# STM32G473CET6_PINOUT.net
KiCad netlist of a schematic drawn in Altium Designer
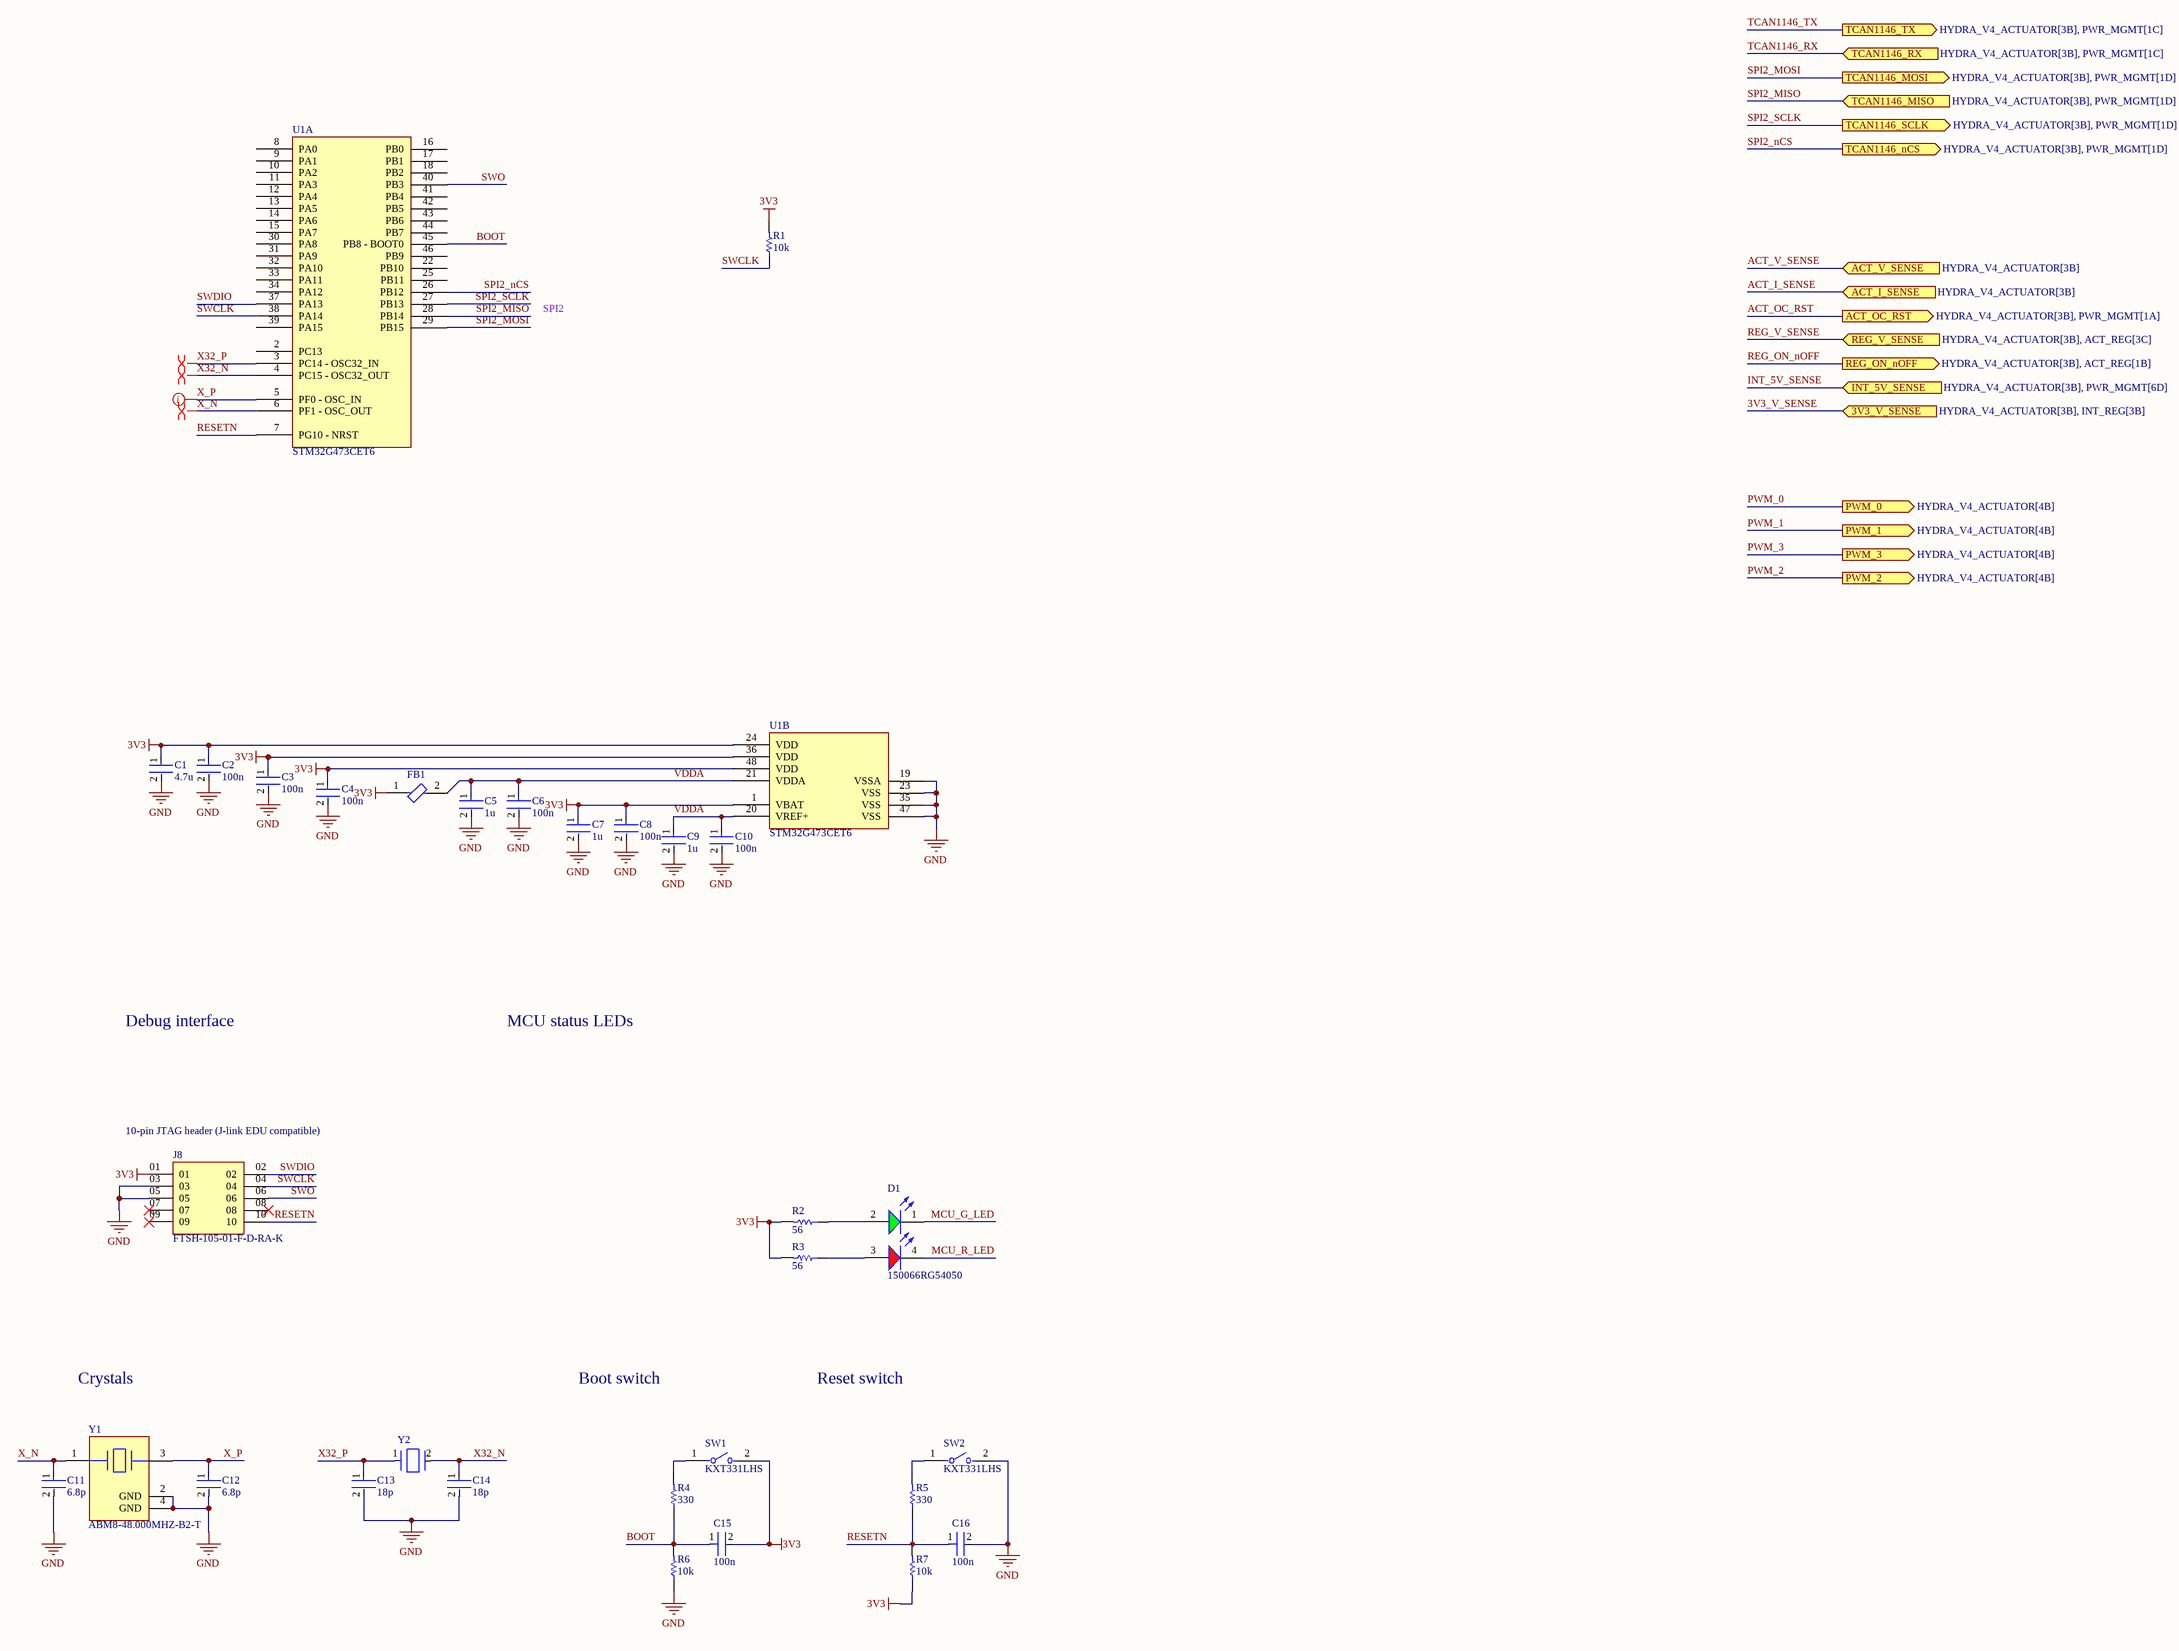
[diagram p0: STM32G473CET6_PINOUT.SchDoc]

(export (version "E")
  (design (tool "Eeschema 10.0.6"))
  (components
    (comp (ref "C1")
      (value "4.7u")
      (footprint "FP-0402-L_1_0_0_05-W_0_5-IPC_A")
      (description "LARGE PADS, 0402 CAP, CHANGE COMMENT TO MATCH REAL P/N")
      (libsource (lib "Space Concordia") (part "b4654b650e69147ec39a6b967a45e02"))
    )
    (comp (ref "C2")
      (value "100n")
      (footprint "FP-0402-L_1_0_0_05-W_0_5-IPC_A")
      (description "LARGE PADS, 0402 CAP, CHANGE COMMENT TO MATCH REAL P/N")
      (libsource (lib "Space Concordia") (part "b4654b650e69147ec39a6b967a45e02"))
    )
    (comp (ref "C3")
      (value "100n")
      (footprint "FP-0402-L_1_0_0_05-W_0_5-IPC_A")
      (description "LARGE PADS, 0402 CAP, CHANGE COMMENT TO MATCH REAL P/N")
      (libsource (lib "Space Concordia") (part "b4654b650e69147ec39a6b967a45e02"))
    )
    (comp (ref "C4")
      (value "100n")
      (footprint "FP-0402-L_1_0_0_05-W_0_5-IPC_A")
      (description "LARGE PADS, 0402 CAP, CHANGE COMMENT TO MATCH REAL P/N")
      (libsource (lib "Space Concordia") (part "b4654b650e69147ec39a6b967a45e02"))
    )
    (comp (ref "C5")
      (value "1u")
      (footprint "FP-0402-L_1_0_0_05-W_0_5-IPC_A")
      (description "LARGE PADS, 0402 CAP, CHANGE COMMENT TO MATCH REAL P/N")
      (libsource (lib "Space Concordia") (part "b4654b650e69147ec39a6b967a45e02"))
    )
    (comp (ref "C6")
      (value "100n")
      (footprint "FP-0402-L_1_0_0_05-W_0_5-IPC_A")
      (description "LARGE PADS, 0402 CAP, CHANGE COMMENT TO MATCH REAL P/N")
      (libsource (lib "Space Concordia") (part "b4654b650e69147ec39a6b967a45e02"))
    )
    (comp (ref "C7")
      (value "1u")
      (footprint "FP-0402-L_1_0_0_05-W_0_5-IPC_A")
      (description "LARGE PADS, 0402 CAP, CHANGE COMMENT TO MATCH REAL P/N")
      (libsource (lib "Space Concordia") (part "b4654b650e69147ec39a6b967a45e02"))
    )
    (comp (ref "C8")
      (value "100n")
      (footprint "FP-0402-L_1_0_0_05-W_0_5-IPC_A")
      (description "LARGE PADS, 0402 CAP, CHANGE COMMENT TO MATCH REAL P/N")
      (libsource (lib "Space Concordia") (part "b4654b650e69147ec39a6b967a45e02"))
    )
    (comp (ref "C9")
      (value "1u")
      (footprint "FP-0402-L_1_0_0_05-W_0_5-IPC_A")
      (description "LARGE PADS, 0402 CAP, CHANGE COMMENT TO MATCH REAL P/N")
      (libsource (lib "Space Concordia") (part "b4654b650e69147ec39a6b967a45e02"))
    )
    (comp (ref "C10")
      (value "100n")
      (footprint "FP-0402-L_1_0_0_05-W_0_5-IPC_A")
      (description "LARGE PADS, 0402 CAP, CHANGE COMMENT TO MATCH REAL P/N")
      (libsource (lib "Space Concordia") (part "b4654b650e69147ec39a6b967a45e02"))
    )
    (comp (ref "C11")
      (value "6.8p")
      (footprint "FP-0402-L_1_0_0_05-W_0_5-IPC_A")
      (description "LARGE PADS, 0402 CAP, CHANGE COMMENT TO MATCH REAL P/N")
      (libsource (lib "Space Concordia") (part "b4654b650e69147ec39a6b967a45e02"))
    )
    (comp (ref "C12")
      (value "6.8p")
      (footprint "FP-0402-L_1_0_0_05-W_0_5-IPC_A")
      (description "LARGE PADS, 0402 CAP, CHANGE COMMENT TO MATCH REAL P/N")
      (libsource (lib "Space Concordia") (part "b4654b650e69147ec39a6b967a45e02"))
    )
    (comp (ref "C13")
      (value "18p")
      (footprint "FP-0402-L_1_0_0_05-W_0_5-IPC_A")
      (description "LARGE PADS, 0402 CAP, CHANGE COMMENT TO MATCH REAL P/N")
      (libsource (lib "Space Concordia") (part "b4654b650e69147ec39a6b967a45e02"))
    )
    (comp (ref "C14")
      (value "18p")
      (footprint "FP-0402-L_1_0_0_05-W_0_5-IPC_A")
      (description "LARGE PADS, 0402 CAP, CHANGE COMMENT TO MATCH REAL P/N")
      (libsource (lib "Space Concordia") (part "b4654b650e69147ec39a6b967a45e02"))
    )
    (comp (ref "C15")
      (value "100n")
      (footprint "FP-0402-L_1_0_0_05-W_0_5-IPC_A")
      (description "LARGE PADS, 0402 CAP, CHANGE COMMENT TO MATCH REAL P/N")
      (libsource (lib "Space Concordia") (part "b4654b650e69147ec39a6b967a45e02"))
    )
    (comp (ref "C16")
      (value "100n")
      (footprint "FP-0402-L_1_0_0_05-W_0_5-IPC_A")
      (description "LARGE PADS, 0402 CAP, CHANGE COMMENT TO MATCH REAL P/N")
      (libsource (lib "Space Concordia") (part "b4654b650e69147ec39a6b967a45e02"))
    )
    (comp (ref "D1")
      (value "150066RG54050")
      (footprint "WL-SBCD_0606")
      (description "Led, Red/Grn, 180Mcd/230Mcd, 624Nm/525Nm Rohs Compliant: Yes")
      (fields (field (name "SOURCE") "rgled.SchLib"))
      (libsource (lib "Space Concordia") (part "CMP-004-00034-2"))
    )
    (comp (ref "FB1")
      (value "BLM15PX601SN1D")
      (footprint "FP-BLM15-0_05-MFG")
      (description "Chip Ferrite Bead, 0402, 600Ω @ 100MHz, 0.23Ω, 25%, 900mA")
      (fields (field (name "TOLERANCE") "25%"))
      (libsource (lib "Altium Content Vault") (part "5f30dd21d616792df468990f7003faa"))
    )
    (comp (ref "J8")
      (value "FTSH-105-01-F-D-RA-K")
      (footprint "FTSH-105-01-F-D-RA-K-Footprint-1")
      (libsource (lib "Space Concordia") (part "FTSH-105-01-F-D-RA-K-Symbol-1"))
    )
    (comp (ref "R1")
      (value "10k")
      (footprint "R0603B")
      (description "Resistor")
      (libsource (lib "Space Concordia") (part "Resistor"))
    )
    (comp (ref "R2")
      (value "56")
      (footprint "R0603B")
      (description "Resistor")
      (libsource (lib "Space Concordia") (part "Resistor"))
    )
    (comp (ref "R3")
      (value "56")
      (footprint "R0603B")
      (description "Resistor")
      (libsource (lib "Space Concordia") (part "Resistor"))
    )
    (comp (ref "R4")
      (value "330")
      (footprint "R0603B")
      (description "Resistor")
      (libsource (lib "Space Concordia") (part "Resistor"))
    )
    (comp (ref "R5")
      (value "330")
      (footprint "R0603B")
      (description "Resistor")
      (libsource (lib "Space Concordia") (part "Resistor"))
    )
    (comp (ref "R6")
      (value "10k")
      (footprint "R0603B")
      (description "Resistor")
      (libsource (lib "Space Concordia") (part "Resistor"))
    )
    (comp (ref "R7")
      (value "10k")
      (footprint "R0603B")
      (description "Resistor")
      (libsource (lib "Space Concordia") (part "Resistor"))
    )
    (comp (ref "SW1")
      (value "KXT331LHS")
      (footprint "FP-KXT331LHS-MFG")
      (description "SWITCH TACTILE SPST-NO 0.02A 15V")
      (libsource (lib "Altium Content Vault") (part "bb27bde45df87f1f469753f287ef5ae"))
    )
    (comp (ref "SW2")
      (value "KXT331LHS")
      (footprint "FP-KXT331LHS-MFG")
      (description "SWITCH TACTILE SPST-NO 0.02A 15V")
      (libsource (lib "Altium Content Vault") (part "bb27bde45df87f1f469753f287ef5ae"))
    )
    (comp (ref "U1")
      (value "STM32G473CET6")
      (footprint "TSQFP50P900X900X160-48N")
      (description "RISC Microcontroller, 32-Bit, 170MHz")
      (libsource (lib "Space Concordia") (part "STM32G473CET6"))
    )
    (comp (ref "Y1")
      (value "ABM8-48.000MHZ-B2-T")
      (footprint "FP-ABM8-MFG")
      (description "Crystal 48MHz ±20ppm 18pF SMD-4 3.2mm x 2.5mm")
      (fields (field (name "TOLERANCE") "20ppm"))
      (libsource (lib "Altium Content Vault") (part "dfdb7f9a12507849fb681da9a70121c"))
    )
    (comp (ref "Y2")
      (value "ECS-.327-12.5-1210-TR")
      (footprint "FP-ECX-1210-MFG")
      (description "CRYSTAL 32.7680KHZ 12.5PF SMD")
      (fields
        (field (name "OCTOPART") "https://octopart.com/ecs-.327-12.5-1210-tr-ecs+international-81221340")
        (field (name "TOLERANCE") "20ppm")
      )
      (libsource (lib "Altium Content Vault") (part "99724985039315a44fd0d1401b84e49"))
    )
  )
  (nets
    (net (code "5") (name "/BOOT") (class "Default")
      (node (ref "C15") (pin "1") (pinfunction "1_1") (pintype "passive"))
      (node (ref "R4") (pin "1") (pinfunction "1_1") (pintype "passive"))
      (node (ref "R6") (pin "2") (pinfunction "2_2") (pintype "passive"))
      (node (ref "U1") (pin "45") (pinfunction "PB8_-_BOOT0_45") (pintype "passive"))
    )
    (net (code "7") (name "/MCU_G_LED") (class "Default")
      (node (ref "D1") (pin "1") (pinfunction "K_1") (pintype "passive"))
    )
    (net (code "8") (name "/MCU_R_LED") (class "Default")
      (node (ref "D1") (pin "4") (pinfunction "K_4") (pintype "passive"))
    )
    (net (code "15") (name "/RESETN") (class "Default")
      (node (ref "C16") (pin "1") (pinfunction "1_1") (pintype "passive"))
      (node (ref "J8") (pin "10") (pinfunction "10_10") (pintype "passive"))
      (node (ref "R5") (pin "1") (pinfunction "1_1") (pintype "passive"))
      (node (ref "R7") (pin "2") (pinfunction "2_2") (pintype "passive"))
      (node (ref "U1") (pin "7") (pinfunction "PG10_-_NRST_7") (pintype "passive"))
    )
    (net (code "16") (name "/SPI2_MISO") (class "Default")
      (node (ref "U1") (pin "28") (pinfunction "PB14_28") (pintype "passive"))
    )
    (net (code "17") (name "/SPI2_MOSI") (class "Default")
      (node (ref "U1") (pin "29") (pinfunction "PB15_29") (pintype "passive"))
    )
    (net (code "18") (name "/SPI2_SCLK") (class "Default")
      (node (ref "U1") (pin "27") (pinfunction "PB13_27") (pintype "passive"))
    )
    (net (code "19") (name "/SPI2_nCS") (class "Default")
      (node (ref "U1") (pin "26") (pinfunction "PB12_26") (pintype "passive"))
    )
    (net (code "20") (name "/SWCLK") (class "Default")
      (node (ref "J8") (pin "04") (pinfunction "04_04") (pintype "passive"))
      (node (ref "R1") (pin "1") (pinfunction "1_1") (pintype "passive"))
      (node (ref "U1") (pin "38") (pinfunction "PA14_38") (pintype "passive"))
    )
    (net (code "21") (name "/SWDIO") (class "Default")
      (node (ref "J8") (pin "02") (pinfunction "02_02") (pintype "passive"))
      (node (ref "U1") (pin "37") (pinfunction "PA13_37") (pintype "passive"))
    )
    (net (code "22") (name "/SWO") (class "Default")
      (node (ref "J8") (pin "06") (pinfunction "06_06") (pintype "passive"))
      (node (ref "U1") (pin "40") (pinfunction "PB3_40") (pintype "passive"))
    )
    (net (code "25") (name "/VDDA") (class "Default")
      (node (ref "C10") (pin "1") (pinfunction "1_1") (pintype "passive"))
      (node (ref "C5") (pin "1") (pinfunction "1_1") (pintype "passive"))
      (node (ref "C6") (pin "1") (pinfunction "1_1") (pintype "passive"))
      (node (ref "C9") (pin "1") (pinfunction "1_1") (pintype "passive"))
      (node (ref "FB1") (pin "2") (pinfunction "2_2") (pintype "passive"))
      (node (ref "U1") (pin "20") (pinfunction "VREF+_20") (pintype "passive"))
      (node (ref "U1") (pin "21") (pinfunction "VDDA_21") (pintype "passive"))
    )
    (net (code "26") (name "/X32_N") (class "Default")
      (node (ref "C14") (pin "1") (pinfunction "1_1") (pintype "passive"))
      (node (ref "U1") (pin "4") (pinfunction "PC15_-_OSC32_OUT_4") (pintype "passive"))
      (node (ref "Y2") (pin "2") (pinfunction "Out/In_2") (pintype "passive"))
    )
    (net (code "27") (name "/X32_P") (class "Default")
      (node (ref "C13") (pin "1") (pinfunction "1_1") (pintype "passive"))
      (node (ref "U1") (pin "3") (pinfunction "PC14_-_OSC32_IN_3") (pintype "passive"))
      (node (ref "Y2") (pin "1") (pinfunction "In/Out_1") (pintype "passive"))
    )
    (net (code "28") (name "/X_N") (class "Default")
      (node (ref "C11") (pin "1") (pinfunction "1_1") (pintype "passive"))
      (node (ref "U1") (pin "6") (pinfunction "PF1_-_OSC_OUT_6") (pintype "passive"))
      (node (ref "Y1") (pin "1") (pinfunction "1_1") (pintype "passive"))
    )
    (net (code "29") (name "/X_P") (class "Default")
      (node (ref "C12") (pin "1") (pinfunction "1_1") (pintype "passive"))
      (node (ref "U1") (pin "5") (pinfunction "PF0_-_OSC_IN_5") (pintype "passive"))
      (node (ref "Y1") (pin "3") (pinfunction "3_3") (pintype "passive"))
    )
    (net (code "30") (name "3V3") (class "Default")
      (node (ref "C1") (pin "1") (pinfunction "1_1") (pintype "passive"))
      (node (ref "C15") (pin "2") (pinfunction "2_2") (pintype "passive"))
      (node (ref "C2") (pin "1") (pinfunction "1_1") (pintype "passive"))
      (node (ref "C3") (pin "1") (pinfunction "1_1") (pintype "passive"))
      (node (ref "C4") (pin "1") (pinfunction "1_1") (pintype "passive"))
      (node (ref "C7") (pin "1") (pinfunction "1_1") (pintype "passive"))
      (node (ref "C8") (pin "1") (pinfunction "1_1") (pintype "passive"))
      (node (ref "FB1") (pin "1") (pinfunction "1_1") (pintype "passive"))
      (node (ref "J8") (pin "01") (pinfunction "01_01") (pintype "passive"))
      (node (ref "R1") (pin "2") (pinfunction "2_2") (pintype "passive"))
      (node (ref "R2") (pin "2") (pinfunction "2_2") (pintype "passive"))
      (node (ref "R3") (pin "2") (pinfunction "2_2") (pintype "passive"))
      (node (ref "R7") (pin "1") (pinfunction "1_1") (pintype "passive"))
      (node (ref "SW1") (pin "2") (pinfunction "2_2") (pintype "passive"))
      (node (ref "U1") (pin "1") (pinfunction "VBAT_1") (pintype "passive"))
      (node (ref "U1") (pin "24") (pinfunction "VDD_24") (pintype "passive"))
      (node (ref "U1") (pin "36") (pinfunction "VDD_36") (pintype "passive"))
      (node (ref "U1") (pin "48") (pinfunction "VDD_48") (pintype "passive"))
    )
    (net (code "31") (name "GND") (class "Default")
      (node (ref "C1") (pin "2") (pinfunction "2_2") (pintype "passive"))
      (node (ref "C10") (pin "2") (pinfunction "2_2") (pintype "passive"))
      (node (ref "C11") (pin "2") (pinfunction "2_2") (pintype "passive"))
      (node (ref "C12") (pin "2") (pinfunction "2_2") (pintype "passive"))
      (node (ref "C13") (pin "2") (pinfunction "2_2") (pintype "passive"))
      (node (ref "C14") (pin "2") (pinfunction "2_2") (pintype "passive"))
      (node (ref "C16") (pin "2") (pinfunction "2_2") (pintype "passive"))
      (node (ref "C2") (pin "2") (pinfunction "2_2") (pintype "passive"))
      (node (ref "C3") (pin "2") (pinfunction "2_2") (pintype "passive"))
      (node (ref "C4") (pin "2") (pinfunction "2_2") (pintype "passive"))
      (node (ref "C5") (pin "2") (pinfunction "2_2") (pintype "passive"))
      (node (ref "C6") (pin "2") (pinfunction "2_2") (pintype "passive"))
      (node (ref "C7") (pin "2") (pinfunction "2_2") (pintype "passive"))
      (node (ref "C8") (pin "2") (pinfunction "2_2") (pintype "passive"))
      (node (ref "C9") (pin "2") (pinfunction "2_2") (pintype "passive"))
      (node (ref "J8") (pin "03") (pinfunction "03_03") (pintype "passive"))
      (node (ref "J8") (pin "05") (pinfunction "05_05") (pintype "passive"))
      (node (ref "R6") (pin "1") (pinfunction "1_1") (pintype "passive"))
      (node (ref "SW2") (pin "2") (pinfunction "2_2") (pintype "passive"))
      (node (ref "U1") (pin "19") (pinfunction "VSSA_19") (pintype "passive"))
      (node (ref "U1") (pin "23") (pinfunction "VSS_23") (pintype "passive"))
      (node (ref "U1") (pin "35") (pinfunction "VSS_35") (pintype "passive"))
      (node (ref "U1") (pin "47") (pinfunction "VSS_47") (pintype "passive"))
      (node (ref "Y1") (pin "2") (pinfunction "GND_2") (pintype "power_in"))
      (node (ref "Y1") (pin "4") (pinfunction "GND_4") (pintype "power_in"))
    )
    (net (code "32") (name "Net-(D1-A-Pad2)") (class "Default")
      (node (ref "D1") (pin "2") (pinfunction "A_2") (pintype "passive"))
      (node (ref "R2") (pin "1") (pinfunction "1_1") (pintype "passive"))
    )
    (net (code "33") (name "Net-(D1-A-Pad3)") (class "Default")
      (node (ref "D1") (pin "3") (pinfunction "A_3") (pintype "passive"))
      (node (ref "R3") (pin "1") (pinfunction "1_1") (pintype "passive"))
    )
    (net (code "34") (name "Net-(R4-Pad2)") (class "Default")
      (node (ref "R4") (pin "2") (pinfunction "2_2") (pintype "passive"))
      (node (ref "SW1") (pin "1") (pinfunction "1_1") (pintype "passive"))
    )
    (net (code "35") (name "Net-(R5-Pad2)") (class "Default")
      (node (ref "R5") (pin "2") (pinfunction "2_2") (pintype "passive"))
      (node (ref "SW2") (pin "1") (pinfunction "1_1") (pintype "passive"))
    )
    (net (code "36") (name "unconnected-(J8-Pad07)") (class "Default")
      (node (ref "J8") (pin "07") (pinfunction "07_07") (pintype "passive+no_connect"))
    )
    (net (code "37") (name "unconnected-(J8-Pad08)") (class "Default")
      (node (ref "J8") (pin "08") (pinfunction "08_08") (pintype "passive+no_connect"))
    )
    (net (code "38") (name "unconnected-(J8-Pad09)") (class "Default")
      (node (ref "J8") (pin "09") (pinfunction "09_09") (pintype "passive+no_connect"))
    )
    (net (code "39") (name "unconnected-(U1A-PA0-Pad8)") (class "Default")
      (node (ref "U1") (pin "8") (pinfunction "PA0_8") (pintype "passive"))
    )
    (net (code "40") (name "unconnected-(U1A-PA1-Pad9)") (class "Default")
      (node (ref "U1") (pin "9") (pinfunction "PA1_9") (pintype "passive"))
    )
    (net (code "41") (name "unconnected-(U1A-PA2-Pad10)") (class "Default")
      (node (ref "U1") (pin "10") (pinfunction "PA2_10") (pintype "passive"))
    )
    (net (code "42") (name "unconnected-(U1A-PA3-Pad11)") (class "Default")
      (node (ref "U1") (pin "11") (pinfunction "PA3_11") (pintype "passive"))
    )
    (net (code "43") (name "unconnected-(U1A-PA4-Pad12)") (class "Default")
      (node (ref "U1") (pin "12") (pinfunction "PA4_12") (pintype "passive"))
    )
    (net (code "44") (name "unconnected-(U1A-PA5-Pad13)") (class "Default")
      (node (ref "U1") (pin "13") (pinfunction "PA5_13") (pintype "passive"))
    )
    (net (code "45") (name "unconnected-(U1A-PA6-Pad14)") (class "Default")
      (node (ref "U1") (pin "14") (pinfunction "PA6_14") (pintype "passive"))
    )
    (net (code "46") (name "unconnected-(U1A-PA7-Pad15)") (class "Default")
      (node (ref "U1") (pin "15") (pinfunction "PA7_15") (pintype "passive"))
    )
    (net (code "47") (name "unconnected-(U1A-PA8-Pad30)") (class "Default")
      (node (ref "U1") (pin "30") (pinfunction "PA8_30") (pintype "passive"))
    )
    (net (code "48") (name "unconnected-(U1A-PA9-Pad31)") (class "Default")
      (node (ref "U1") (pin "31") (pinfunction "PA9_31") (pintype "passive"))
    )
    (net (code "49") (name "unconnected-(U1A-PA10-Pad32)") (class "Default")
      (node (ref "U1") (pin "32") (pinfunction "PA10_32") (pintype "passive"))
    )
    (net (code "50") (name "unconnected-(U1A-PA11-Pad33)") (class "Default")
      (node (ref "U1") (pin "33") (pinfunction "PA11_33") (pintype "passive"))
    )
    (net (code "51") (name "unconnected-(U1A-PA12-Pad34)") (class "Default")
      (node (ref "U1") (pin "34") (pinfunction "PA12_34") (pintype "passive"))
    )
    (net (code "52") (name "unconnected-(U1A-PA15-Pad39)") (class "Default")
      (node (ref "U1") (pin "39") (pinfunction "PA15_39") (pintype "passive"))
    )
    (net (code "53") (name "unconnected-(U1A-PB0-Pad16)") (class "Default")
      (node (ref "U1") (pin "16") (pinfunction "PB0_16") (pintype "passive"))
    )
    (net (code "54") (name "unconnected-(U1A-PB1-Pad17)") (class "Default")
      (node (ref "U1") (pin "17") (pinfunction "PB1_17") (pintype "passive"))
    )
    (net (code "55") (name "unconnected-(U1A-PB2-Pad18)") (class "Default")
      (node (ref "U1") (pin "18") (pinfunction "PB2_18") (pintype "passive"))
    )
    (net (code "56") (name "unconnected-(U1A-PB4-Pad41)") (class "Default")
      (node (ref "U1") (pin "41") (pinfunction "PB4_41") (pintype "passive"))
    )
    (net (code "57") (name "unconnected-(U1A-PB5-Pad42)") (class "Default")
      (node (ref "U1") (pin "42") (pinfunction "PB5_42") (pintype "passive"))
    )
    (net (code "58") (name "unconnected-(U1A-PB6-Pad43)") (class "Default")
      (node (ref "U1") (pin "43") (pinfunction "PB6_43") (pintype "passive"))
    )
    (net (code "59") (name "unconnected-(U1A-PB7-Pad44)") (class "Default")
      (node (ref "U1") (pin "44") (pinfunction "PB7_44") (pintype "passive"))
    )
    (net (code "60") (name "unconnected-(U1A-PB9-Pad46)") (class "Default")
      (node (ref "U1") (pin "46") (pinfunction "PB9_46") (pintype "passive"))
    )
    (net (code "61") (name "unconnected-(U1A-PB10-Pad22)") (class "Default")
      (node (ref "U1") (pin "22") (pinfunction "PB10_22") (pintype "passive"))
    )
    (net (code "62") (name "unconnected-(U1A-PB11-Pad25)") (class "Default")
      (node (ref "U1") (pin "25") (pinfunction "PB11_25") (pintype "passive"))
    )
    (net (code "63") (name "unconnected-(U1A-PC13-Pad2)") (class "Default")
      (node (ref "U1") (pin "2") (pinfunction "PC13_2") (pintype "passive"))
    )
  )
)
